# Sensors_Actuators.net
KiCad netlist of a schematic drawn in Altium Designer
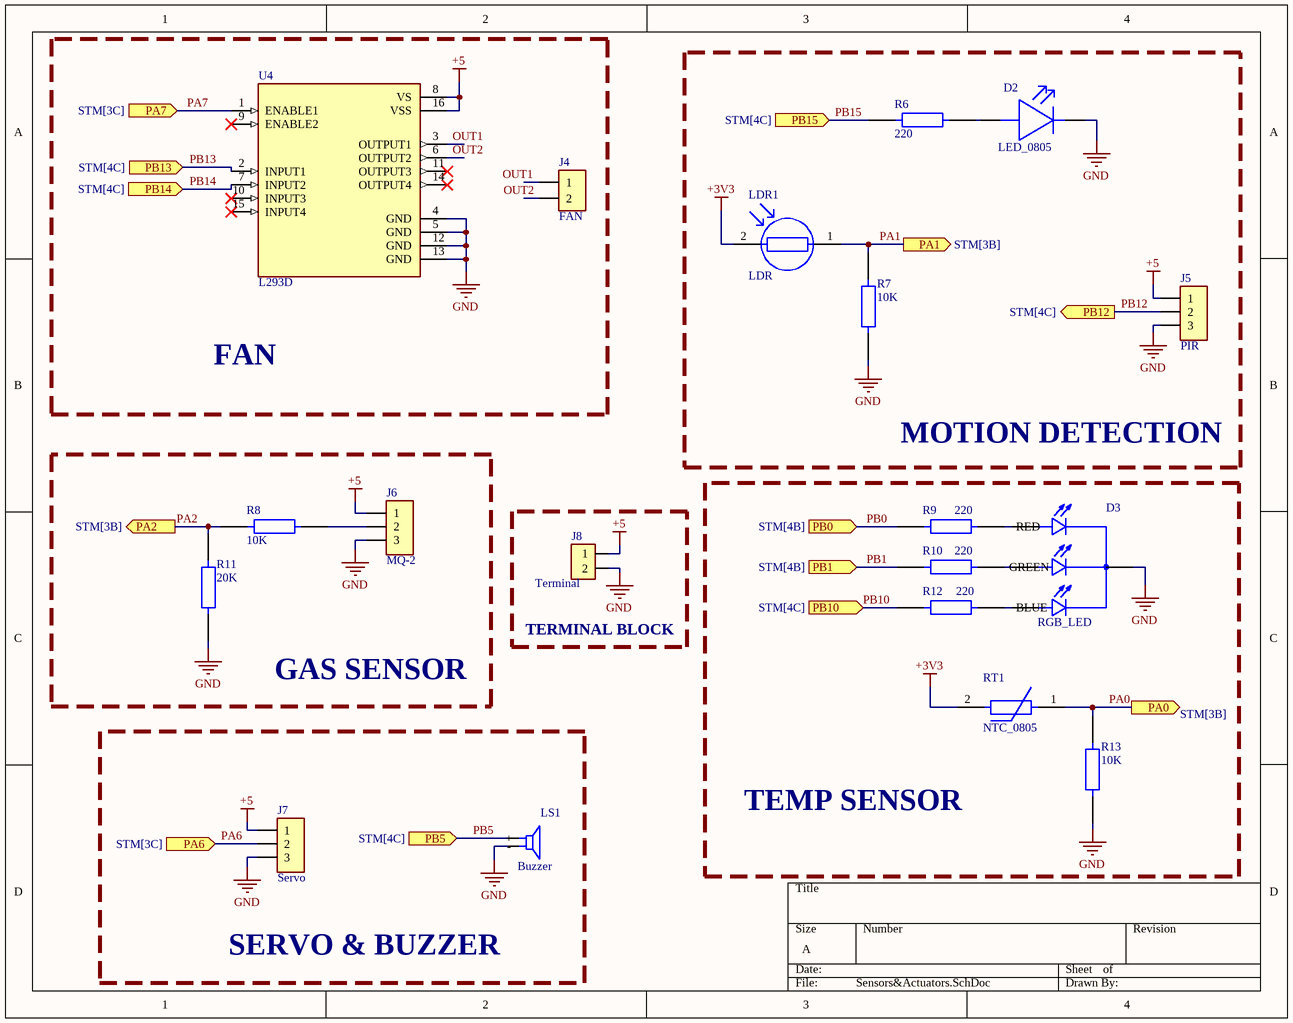
[diagram p0: Sensors&Actuators.SchDoc]

(export (version "E")
  (design (tool "Eeschema 10.0.6"))
  (components
    (comp (ref "D2")
      (value "LED_0805")
      (footprint "LED_0805")
      (description "LED RED 0805 SMD")
      (fields (field (name "MFR") "YONGYUTAI") (field (name "MFR PART#") "YLED0805R"))
      (libsource (lib "project") (part "LED_0805"))
    )
    (comp (ref "D3")
      (value "RGB_LED")
      (footprint "RGB_LED")
      (description "TriColor ChipLED")
      (fields (field (name "MFR") "Broadcom") (field (name "MFR PART#") "HSMF-C118"))
      (libsource (lib "project") (part "RGB_LED"))
    )
    (comp (ref "J4")
      (value "FAN")
      (footprint "pin_header_2")
      (fields
        (field (name "MFR") "hanxia")
        (field (name "MFR PART#") "HX PH254-01-03-Z-L11.5 pcb pin header")
      )
      (libsource (lib "project") (part "pin_header_2"))
    )
    (comp (ref "J5")
      (value "PIR")
      (footprint "pin_header_3")
      (fields
        (field (name "MFR") "hanxia")
        (field (name "MFR PART#") "HX PH254-01-03-Z-L11.5 pcb pin header")
      )
      (libsource (lib "project") (part "pin_header_3"))
    )
    (comp (ref "J6")
      (value "MQ-2")
      (footprint "pin_header_3")
      (fields
        (field (name "MFR") "hanxia")
        (field (name "MFR PART#") "HX PH254-01-03-Z-L11.5 pcb pin header")
      )
      (libsource (lib "project") (part "pin_header_3"))
    )
    (comp (ref "J7")
      (value "Servo")
      (footprint "pin_header_3")
      (fields
        (field (name "MFR") "hanxia")
        (field (name "MFR PART#") "HX PH254-01-03-Z-L11.5 pcb pin header")
      )
      (libsource (lib "project") (part "pin_header_3"))
    )
    (comp (ref "J8")
      (value "Terminal")
      (footprint "Terminal")
      (description "TERM BLK 2POS 5.08mm TH")
      (fields (field (name "MFR") "KANGNEX") (field (name "MFR PART#") "WJ500V-5.08-2P"))
      (libsource (lib "project") (part "Terminal"))
    )
    (comp (ref "LDR1")
      (value "LDR")
      (footprint "LDR")
      (description "Photoconductive Cell")
      (fields (field (name "MFR") "JCHL") (field (name "MFR PART#") "GT36516"))
      (libsource (lib "project") (part "LDR"))
    )
    (comp (ref "LS1")
      (value "Buzzer")
      (footprint "Buzzer")
      (description "Active Buzzer (Built-in Driving Circuit) 2.3kHz 5V Electromagnetic Alarms, Buzzers, and Sirens")
      (fields (field (name "MFR") "CUI") (field (name "MFR PART#") "CMI-1295-0585T"))
      (libsource (lib "project") (part "Buzzer"))
    )
    (comp (ref "R6")
      (value "220")
      (footprint "RES_0805")
      (description "RES 220Ω ±0.1% 125mW 0805")
      (fields (field (name "MFR") "YAGEO") (field (name "MFR PART#") "RT0805BRD07220RL"))
      (libsource (lib "project") (part "RES_0805_220"))
    )
    (comp (ref "R7")
      (value "10K")
      (footprint "RES_0805")
      (description "RES 10kΩ ±0.1% 125mW 0805")
      (fields (field (name "MFR") "YAGEO") (field (name "MFR PART#") "RT0805BRD0710KL"))
      (libsource (lib "project") (part "RES_0805_10K"))
    )
    (comp (ref "R8")
      (value "10K")
      (footprint "RES_0805")
      (description "RES 10kΩ ±0.1% 125mW 0805")
      (fields (field (name "MFR") "YAGEO") (field (name "MFR PART#") "RT0805BRD0710KL"))
      (libsource (lib "project") (part "RES_0805_10K"))
    )
    (comp (ref "R9")
      (value "220")
      (footprint "RES_0805")
      (description "RES 220Ω ±0.1% 125mW 0805")
      (fields (field (name "MFR") "YAGEO") (field (name "MFR PART#") "RT0805BRD07220RL"))
      (libsource (lib "project") (part "RES_0805_220"))
    )
    (comp (ref "R10")
      (value "220")
      (footprint "RES_0805")
      (description "RES 220Ω ±0.1% 125mW 0805")
      (fields (field (name "MFR") "YAGEO") (field (name "MFR PART#") "RT0805BRD07220RL"))
      (libsource (lib "project") (part "RES_0805_220"))
    )
    (comp (ref "R11")
      (value "20K")
      (footprint "RES_0805")
      (description "RES 20kΩ ±1% 125mW 0805")
      (fields (field (name "MFR") "YAGEO") (field (name "MFR PART#") "RC0805FR-0720KL"))
      (libsource (lib "project") (part "RES_0805_20K"))
    )
    (comp (ref "R12")
      (value "220")
      (footprint "RES_0805")
      (description "RES 220Ω ±0.1% 125mW 0805")
      (fields (field (name "MFR") "YAGEO") (field (name "MFR PART#") "RT0805BRD07220RL"))
      (libsource (lib "project") (part "RES_0805_220"))
    )
    (comp (ref "R13")
      (value "10K")
      (footprint "RES_0805")
      (description "RES 10kΩ ±0.1% 125mW 0805")
      (fields (field (name "MFR") "YAGEO") (field (name "MFR PART#") "RT0805BRD0710KL"))
      (libsource (lib "project") (part "RES_0805_10K"))
    )
    (comp (ref "RT1")
      (value "NTC_0805")
      (footprint "NTC_0805")
      (description "THERMISTOR NTC 10kΩ 0805")
      (fields (field (name "MFR") "VISHAY") (field (name "MFR PART#") "NTCS0805E3103JHT"))
      (libsource (lib "project") (part "NTC_0805"))
    )
    (comp (ref "U4")
      (value "L293D")
      (footprint "L293D")
      (description "PUSH-PULL FOUR CHANNEL DRIVER WITH DIODES")
      (fields (field (name "MFR") "ST"))
      (libsource (lib "project") (part "L293D"))
    )
  )
  (nets
    (net (code "1") (name "+3V3") (class "Default")
      (node (ref "LDR1") (pin "2") (pinfunction "2_2") (pintype "passive"))
      (node (ref "RT1") (pin "2") (pinfunction "2_2") (pintype "passive"))
    )
    (net (code "2") (name "+5") (class "Default")
      (node (ref "J5") (pin "1") (pinfunction "1_1") (pintype "passive"))
      (node (ref "J6") (pin "1") (pinfunction "1_1") (pintype "passive"))
      (node (ref "J7") (pin "1") (pinfunction "1_1") (pintype "passive"))
      (node (ref "J8") (pin "1") (pinfunction "1_1") (pintype "passive"))
      (node (ref "U4") (pin "16") (pinfunction "VSS_16") (pintype "power_in"))
      (node (ref "U4") (pin "8") (pinfunction "VS_8") (pintype "power_in"))
    )
    (net (code "3") (name "/OUT1") (class "Default")
      (node (ref "J4") (pin "1") (pinfunction "1_1") (pintype "passive"))
      (node (ref "U4") (pin "3") (pinfunction "OUTPUT1_3") (pintype "output"))
    )
    (net (code "4") (name "/OUT2") (class "Default")
      (node (ref "J4") (pin "2") (pinfunction "2_2") (pintype "passive"))
      (node (ref "U4") (pin "6") (pinfunction "OUTPUT2_6") (pintype "output"))
    )
    (net (code "5") (name "/PA0") (class "Default")
      (node (ref "R13") (pin "1") (pinfunction "1_1") (pintype "passive"))
      (node (ref "RT1") (pin "1") (pinfunction "1_1") (pintype "passive"))
    )
    (net (code "6") (name "/PA1") (class "Default")
      (node (ref "LDR1") (pin "1") (pinfunction "1_1") (pintype "passive"))
      (node (ref "R7") (pin "1") (pinfunction "1_1") (pintype "passive"))
    )
    (net (code "7") (name "/PA2") (class "Default")
      (node (ref "R11") (pin "1") (pinfunction "1_1") (pintype "passive"))
      (node (ref "R8") (pin "2") (pinfunction "2_2") (pintype "passive"))
    )
    (net (code "8") (name "/PA6") (class "Default")
      (node (ref "J7") (pin "2") (pinfunction "2_2") (pintype "passive"))
    )
    (net (code "9") (name "/PA7") (class "Default")
      (node (ref "U4") (pin "1") (pinfunction "ENABLE1_1") (pintype "input"))
    )
    (net (code "10") (name "/PB0") (class "Default")
      (node (ref "R9") (pin "2") (pinfunction "2_2") (pintype "passive"))
    )
    (net (code "11") (name "/PB1") (class "Default")
      (node (ref "R10") (pin "2") (pinfunction "2_2") (pintype "passive"))
    )
    (net (code "12") (name "/PB5") (class "Default")
      (node (ref "LS1") (pin "1") (pinfunction "+_1") (pintype "passive"))
    )
    (net (code "13") (name "/PB10") (class "Default")
      (node (ref "R12") (pin "2") (pinfunction "2_2") (pintype "passive"))
    )
    (net (code "14") (name "/PB12") (class "Default")
      (node (ref "J5") (pin "2") (pinfunction "2_2") (pintype "passive"))
    )
    (net (code "15") (name "/PB13") (class "Default")
      (node (ref "U4") (pin "2") (pinfunction "INPUT1_2") (pintype "input"))
    )
    (net (code "16") (name "/PB14") (class "Default")
      (node (ref "U4") (pin "7") (pinfunction "INPUT2_7") (pintype "input"))
    )
    (net (code "17") (name "/PB15") (class "Default")
      (node (ref "R6") (pin "2") (pinfunction "2_2") (pintype "passive"))
    )
    (net (code "18") (name "GND") (class "Default")
      (node (ref "D2") (pin "2") (pintype "passive"))
      (node (ref "D3") (pin "1") (pinfunction "GND_1") (pintype "passive"))
      (node (ref "J5") (pin "3") (pinfunction "3_3") (pintype "passive"))
      (node (ref "J6") (pin "3") (pinfunction "3_3") (pintype "passive"))
      (node (ref "J7") (pin "3") (pinfunction "3_3") (pintype "passive"))
      (node (ref "J8") (pin "2") (pinfunction "2_2") (pintype "passive"))
      (node (ref "LS1") (pin "2") (pinfunction "-_2") (pintype "passive"))
      (node (ref "R11") (pin "2") (pinfunction "2_2") (pintype "passive"))
      (node (ref "R13") (pin "2") (pinfunction "2_2") (pintype "passive"))
      (node (ref "R7") (pin "2") (pinfunction "2_2") (pintype "passive"))
      (node (ref "U4") (pin "12") (pinfunction "GND_12") (pintype "power_in"))
      (node (ref "U4") (pin "13") (pinfunction "GND_13") (pintype "power_in"))
      (node (ref "U4") (pin "4") (pinfunction "GND_4") (pintype "power_in"))
      (node (ref "U4") (pin "5") (pinfunction "GND_5") (pintype "power_in"))
    )
    (net (code "19") (name "Net-(D2-Pad1)") (class "Default")
      (node (ref "D2") (pin "1") (pintype "passive"))
      (node (ref "R6") (pin "1") (pinfunction "1_1") (pintype "passive"))
    )
    (net (code "20") (name "Net-(D3-BLUE)") (class "Default")
      (node (ref "D3") (pin "4") (pinfunction "BLUE_4") (pintype "passive"))
      (node (ref "R12") (pin "1") (pinfunction "1_1") (pintype "passive"))
    )
    (net (code "21") (name "Net-(D3-GREEN)") (class "Default")
      (node (ref "D3") (pin "3") (pinfunction "GREEN_3") (pintype "passive"))
      (node (ref "R10") (pin "1") (pinfunction "1_1") (pintype "passive"))
    )
    (net (code "22") (name "Net-(D3-RED)") (class "Default")
      (node (ref "D3") (pin "2") (pinfunction "RED_2") (pintype "passive"))
      (node (ref "R9") (pin "1") (pinfunction "1_1") (pintype "passive"))
    )
    (net (code "23") (name "Net-(J6-Pad2)") (class "Default")
      (node (ref "J6") (pin "2") (pinfunction "2_2") (pintype "passive"))
      (node (ref "R8") (pin "1") (pinfunction "1_1") (pintype "passive"))
    )
    (net (code "24") (name "unconnected-(U4-ENABLE2-Pad9)") (class "Default")
      (node (ref "U4") (pin "9") (pinfunction "ENABLE2_9") (pintype "input+no_connect"))
    )
    (net (code "25") (name "unconnected-(U4-INPUT3-Pad10)") (class "Default")
      (node (ref "U4") (pin "10") (pinfunction "INPUT3_10") (pintype "input+no_connect"))
    )
    (net (code "26") (name "unconnected-(U4-INPUT4-Pad15)") (class "Default")
      (node (ref "U4") (pin "15") (pinfunction "INPUT4_15") (pintype "input+no_connect"))
    )
    (net (code "27") (name "unconnected-(U4-OUTPUT3-Pad11)") (class "Default")
      (node (ref "U4") (pin "11") (pinfunction "OUTPUT3_11") (pintype "output+no_connect"))
    )
    (net (code "28") (name "unconnected-(U4-OUTPUT4-Pad14)") (class "Default")
      (node (ref "U4") (pin "14") (pinfunction "OUTPUT4_14") (pintype "output+no_connect"))
    )
  )
)
